# MCU.net
KiCad netlist of a schematic drawn in Altium Designer
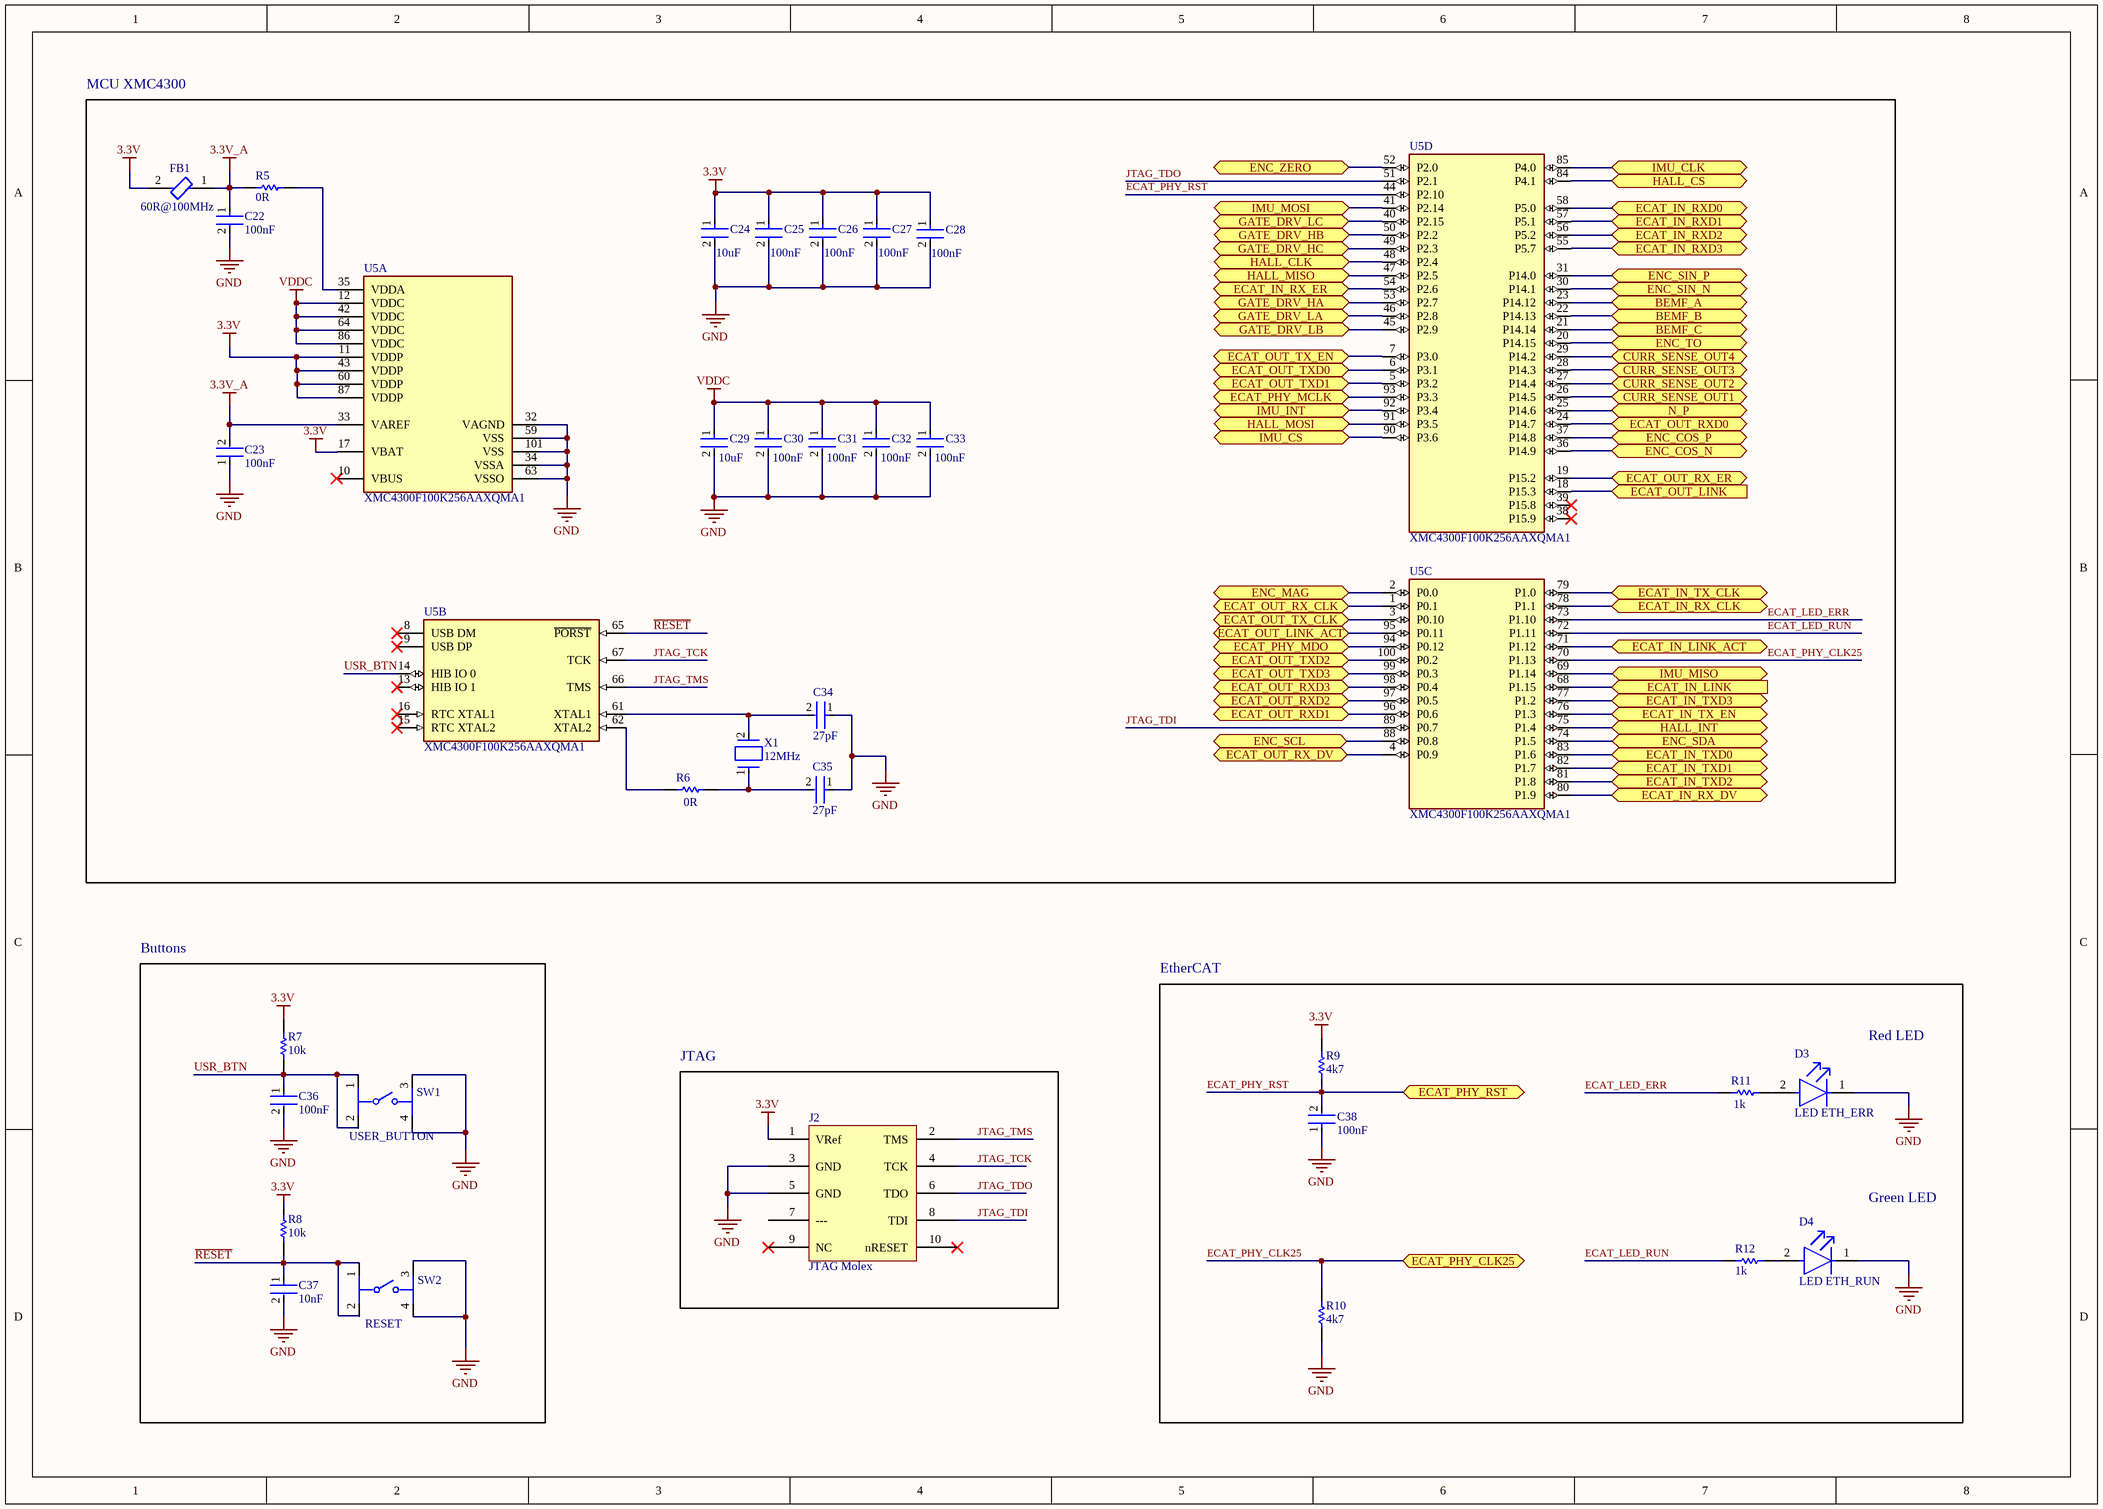
[diagram p0: MCU.SchDoc]

(export (version "E")
  (design (tool "Eeschema 10.0.6"))
  (components
    (comp (ref "C22")
      (value "100nF")
      (footprint "FP-C0805C-DN-MFG")
      (description "CAP CER 0.1UF 50V X7R 0805")
      (fields
        (field (name "MANUFACTURER PART NUMBER") "C0805C104K5RACTU")
        (field (name "MANUFACTURER") "KEMET")
      )
      (libsource (lib "Altium Content Vault") (part "b4654b650e69147ec39a6b967a45e02"))
    )
    (comp (ref "C23")
      (value "100nF")
      (footprint "FP-C0805C-DN-MFG")
      (description "CAP CER 0.1UF 50V X7R 0805")
      (fields
        (field (name "MANUFACTURER PART NUMBER") "C0805C104K5RACTU")
        (field (name "MANUFACTURER") "KEMET")
      )
      (libsource (lib "Altium Content Vault") (part "b4654b650e69147ec39a6b967a45e02"))
    )
    (comp (ref "C24")
      (value "10uF")
      (footprint "FP-C0805C-DN-MFG")
      (description "CAP CER 0.1UF 50V X7R 0805")
      (fields
        (field (name "MANUFACTURER PART NUMBER") "C0805C104K5RACTU")
        (field (name "MANUFACTURER") "KEMET")
      )
      (libsource (lib "Altium Content Vault") (part "b4654b650e69147ec39a6b967a45e02"))
    )
    (comp (ref "C25")
      (value "100nF")
      (footprint "FP-C0805C-DN-MFG")
      (description "CAP CER 0.1UF 50V X7R 0805")
      (fields
        (field (name "MANUFACTURER PART NUMBER") "C0805C104K5RACTU")
        (field (name "MANUFACTURER") "KEMET")
      )
      (libsource (lib "Altium Content Vault") (part "b4654b650e69147ec39a6b967a45e02"))
    )
    (comp (ref "C26")
      (value "100nF")
      (footprint "FP-C0805C-DN-MFG")
      (description "CAP CER 0.1UF 50V X7R 0805")
      (fields
        (field (name "MANUFACTURER PART NUMBER") "C0805C104K5RACTU")
        (field (name "MANUFACTURER") "KEMET")
      )
      (libsource (lib "Altium Content Vault") (part "b4654b650e69147ec39a6b967a45e02"))
    )
    (comp (ref "C27")
      (value "100nF")
      (footprint "FP-C0805C-DN-MFG")
      (description "CAP CER 0.1UF 50V X7R 0805")
      (fields
        (field (name "MANUFACTURER PART NUMBER") "C0805C104K5RACTU")
        (field (name "MANUFACTURER") "KEMET")
      )
      (libsource (lib "Altium Content Vault") (part "b4654b650e69147ec39a6b967a45e02"))
    )
    (comp (ref "C28")
      (value "100nF")
      (footprint "FP-C0805C-DN-MFG")
      (description "CAP CER 0.1UF 50V X7R 0805")
      (fields
        (field (name "MANUFACTURER PART NUMBER") "C0805C104K5RACTU")
        (field (name "MANUFACTURER") "KEMET")
      )
      (libsource (lib "Altium Content Vault") (part "b4654b650e69147ec39a6b967a45e02"))
    )
    (comp (ref "C29")
      (value "10uF")
      (footprint "FP-C0805C-DN-MFG")
      (description "CAP CER 0.1UF 50V X7R 0805")
      (fields
        (field (name "MANUFACTURER PART NUMBER") "C0805C104K5RACTU")
        (field (name "MANUFACTURER") "KEMET")
      )
      (libsource (lib "Altium Content Vault") (part "b4654b650e69147ec39a6b967a45e02"))
    )
    (comp (ref "C30")
      (value "100nF")
      (footprint "FP-C0805C-DN-MFG")
      (description "CAP CER 0.1UF 50V X7R 0805")
      (fields
        (field (name "MANUFACTURER PART NUMBER") "C0805C104K5RACTU")
        (field (name "MANUFACTURER") "KEMET")
      )
      (libsource (lib "Altium Content Vault") (part "b4654b650e69147ec39a6b967a45e02"))
    )
    (comp (ref "C31")
      (value "100nF")
      (footprint "FP-C0805C-DN-MFG")
      (description "CAP CER 0.1UF 50V X7R 0805")
      (fields
        (field (name "MANUFACTURER PART NUMBER") "C0805C104K5RACTU")
        (field (name "MANUFACTURER") "KEMET")
      )
      (libsource (lib "Altium Content Vault") (part "b4654b650e69147ec39a6b967a45e02"))
    )
    (comp (ref "C32")
      (value "100nF")
      (footprint "FP-C0805C-DN-MFG")
      (description "CAP CER 0.1UF 50V X7R 0805")
      (fields
        (field (name "MANUFACTURER PART NUMBER") "C0805C104K5RACTU")
        (field (name "MANUFACTURER") "KEMET")
      )
      (libsource (lib "Altium Content Vault") (part "b4654b650e69147ec39a6b967a45e02"))
    )
    (comp (ref "C33")
      (value "100nF")
      (footprint "FP-C0805C-DN-MFG")
      (description "CAP CER 0.1UF 50V X7R 0805")
      (fields
        (field (name "MANUFACTURER PART NUMBER") "C0805C104K5RACTU")
        (field (name "MANUFACTURER") "KEMET")
      )
      (libsource (lib "Altium Content Vault") (part "b4654b650e69147ec39a6b967a45e02"))
    )
    (comp (ref "C34")
      (value "27pF")
      (footprint "FP-C0805C-DN-MFG")
      (description "CAP CER 0.1UF 50V X7R 0805")
      (fields
        (field (name "MANUFACTURER PART NUMBER") "C0805C104K5RACTU")
        (field (name "MANUFACTURER") "KEMET")
      )
      (libsource (lib "Altium Content Vault") (part "b4654b650e69147ec39a6b967a45e02"))
    )
    (comp (ref "C35")
      (value "27pF")
      (footprint "FP-C0805C-DN-MFG")
      (description "CAP CER 0.1UF 50V X7R 0805")
      (fields
        (field (name "MANUFACTURER PART NUMBER") "C0805C104K5RACTU")
        (field (name "MANUFACTURER") "KEMET")
      )
      (libsource (lib "Altium Content Vault") (part "b4654b650e69147ec39a6b967a45e02"))
    )
    (comp (ref "C36")
      (value "100nF")
      (footprint "FP-C0805C-DN-MFG")
      (description "CAP CER 0.1UF 50V X7R 0805")
      (fields
        (field (name "MANUFACTURER PART NUMBER") "C0805C104K5RACTU")
        (field (name "MANUFACTURER") "KEMET")
      )
      (libsource (lib "Altium Content Vault") (part "b4654b650e69147ec39a6b967a45e02"))
    )
    (comp (ref "C37")
      (value "10nF")
      (footprint "FP-C0805C-DN-MFG")
      (description "CAP CER 0.1UF 50V X7R 0805")
      (fields
        (field (name "MANUFACTURER PART NUMBER") "C0805C104K5RACTU")
        (field (name "MANUFACTURER") "KEMET")
      )
      (libsource (lib "Altium Content Vault") (part "b4654b650e69147ec39a6b967a45e02"))
    )
    (comp (ref "C38")
      (value "100nF")
      (footprint "FP-C0805C-DN-MFG")
      (description "CAP CER 0.1UF 50V X7R 0805")
      (fields
        (field (name "MANUFACTURER PART NUMBER") "C0805C104K5RACTU")
        (field (name "MANUFACTURER") "KEMET")
      )
      (libsource (lib "Altium Content Vault") (part "b4654b650e69147ec39a6b967a45e02"))
    )
    (comp (ref "D3")
      (value "LED ETH_ERR")
      (footprint "FP-LTST-C191GKT-MFG")
      (description "KPHD-1608LVCGCK")
      (libsource (lib "Altium Content Vault") (part "8706943c75ba83719d021d2fdc84c58"))
    )
    (comp (ref "D4")
      (value "LED ETH_RUN")
      (footprint "FP-LTST-C191GKT-MFG")
      (description "KPHD-1608LVCGCK")
      (libsource (lib "Altium Content Vault") (part "8706943c75ba83719d021d2fdc84c58"))
    )
    (comp (ref "FB1")
      (value "60R@100MHz")
      (footprint "FP-BLM18-0_15-t0_8-IPC_C")
      (description "Chip Ferrite Bead, 0603, 60Ω @ 100MHz, 0.1Ω, , 1A\r\n\r\nBLM18PG600SH1D")
      (fields (field (name "TOLERANCE") "25%"))
      (libsource (lib "Altium Content Vault") (part "5f30dd21d616792df468990f7003faa"))
    )
    (comp (ref "J2")
      (value "JTAG Molex")
      (footprint "2X5_JTAG_HEADER")
      (description "MOLEX for JTAG, 5x2, 1,27 mm")
      (libsource (lib "CONNECTOR") (part "5x2_1,27mm_JTAG"))
    )
    (comp (ref "R5")
      (value "0R")
      (footprint "RESC2013X50X30LL20T20")
      (fields (field (name "MANUFACTURER") "Vishay Dale") (field (name "PART NUMBER") "CRCW08050000Z0EA"))
      (libsource (lib "Altium Content Vault") (part "RES"))
    )
    (comp (ref "R6")
      (value "0R")
      (footprint "RESC2013X50X30LL20T20")
      (fields (field (name "MANUFACTURER") "Vishay Dale") (field (name "PART NUMBER") "CRCW08050000Z0EA"))
      (libsource (lib "Altium Content Vault") (part "RES"))
    )
    (comp (ref "R7")
      (value "10k")
      (footprint "RESC2013X50X30LL20T20")
      (fields (field (name "MANUFACTURER") "Vishay Dale") (field (name "PART NUMBER") "CRCW08050000Z0EA"))
      (libsource (lib "Altium Content Vault") (part "RES"))
    )
    (comp (ref "R8")
      (value "10k")
      (footprint "RESC2013X50X30LL20T20")
      (fields (field (name "MANUFACTURER") "Vishay Dale") (field (name "PART NUMBER") "CRCW08050000Z0EA"))
      (libsource (lib "Altium Content Vault") (part "RES"))
    )
    (comp (ref "R9")
      (value "4k7")
      (footprint "RESC2013X50X30LL20T20")
      (description "0805")
      (fields (field (name "MANUFACTURER") "Vishay Dale") (field (name "PART NUMBER") "CRCW08050000Z0EA"))
      (libsource (lib "Altium Content Vault") (part "RES"))
    )
    (comp (ref "R10")
      (value "4k7")
      (footprint "RESC2013X50X30LL20T20")
      (description "0805")
      (fields (field (name "MANUFACTURER") "Vishay Dale") (field (name "PART NUMBER") "CRCW08050000Z0EA"))
      (libsource (lib "Altium Content Vault") (part "RES"))
    )
    (comp (ref "R11")
      (value "1k")
      (footprint "RESC2013X50X30LL20T20")
      (description "0805")
      (fields (field (name "MANUFACTURER") "Vishay Dale") (field (name "PART NUMBER") "CRCW08050000Z0EA"))
      (libsource (lib "Altium Content Vault") (part "RES"))
    )
    (comp (ref "R12")
      (value "1k")
      (footprint "RESC2013X50X30LL20T20")
      (description "0805")
      (fields (field (name "MANUFACTURER") "Vishay Dale") (field (name "PART NUMBER") "CRCW08050000Z0EA"))
      (libsource (lib "Altium Content Vault") (part "RES"))
    )
    (comp (ref "SW1")
      (value "USER_BUTTON")
      (footprint "FP-TL3305AF260QG-MFG")
      (description "SWITCH TACTILE SPST-NO 50MA 12V\r\n\r\nTL3305AF260QG")
      (libsource (lib "Altium Content Vault") (part "b8895f3f4cefb76e1819d2863dba89b"))
    )
    (comp (ref "SW2")
      (value "RESET")
      (footprint "FP-TL3305AF260QG-MFG")
      (description "SWITCH TACTILE SPST-NO 50MA 12V\r\n\r\nTL3305AF260QG")
      (libsource (lib "Altium Content Vault") (part "b8895f3f4cefb76e1819d2863dba89b"))
    )
    (comp (ref "U5")
      (value "XMC4300F100K256AAXQMA1")
      (footprint "FP-PG-LQFP-100-MFG")
      (description "IC MCU 32BIT 256KB FLASH 100LQFP")
      (libsource (lib "Altium Content Vault") (part "f9ed01fb84eaecf55d871649562e8ed"))
    )
    (comp (ref "X1")
      (value "12MHz")
      (footprint "FP-ABM3-MFG")
      (description "Crystal 12MHz SMD-2 5mm x 3.2mm")
      (fields (field (name "TOLERANCE") "20ppm"))
      (libsource (lib "Altium Content Vault") (part "c23a69dc6c9e2f18f2079038eb95dd1"))
    )
  )
  (nets
    (net (code "1") (name "/BEMF_A") (class "Default")
      (node (ref "U5") (pin "23") (pinfunction "P14.12_23") (pintype "bidirectional"))
    )
    (net (code "2") (name "/BEMF_B") (class "Default")
      (node (ref "U5") (pin "22") (pinfunction "P14.13_22") (pintype "bidirectional"))
    )
    (net (code "3") (name "/BEMF_C") (class "Default")
      (node (ref "U5") (pin "21") (pinfunction "P14.14_21") (pintype "bidirectional"))
    )
    (net (code "4") (name "/CURR_SENSE_OUT1") (class "Default")
      (node (ref "U5") (pin "26") (pinfunction "P14.5_26") (pintype "bidirectional"))
    )
    (net (code "5") (name "/CURR_SENSE_OUT2") (class "Default")
      (node (ref "U5") (pin "27") (pinfunction "P14.4_27") (pintype "bidirectional"))
    )
    (net (code "6") (name "/CURR_SENSE_OUT3") (class "Default")
      (node (ref "U5") (pin "28") (pinfunction "P14.3_28") (pintype "bidirectional"))
    )
    (net (code "7") (name "/CURR_SENSE_OUT4") (class "Default")
      (node (ref "U5") (pin "29") (pinfunction "P14.2_29") (pintype "bidirectional"))
    )
    (net (code "8") (name "/ECAT_IN_LINK") (class "Default")
      (node (ref "U5") (pin "68") (pinfunction "P1.15_68") (pintype "bidirectional"))
    )
    (net (code "9") (name "/ECAT_IN_LINK_ACT") (class "Default")
      (node (ref "U5") (pin "71") (pinfunction "P1.12_71") (pintype "bidirectional"))
    )
    (net (code "10") (name "/ECAT_IN_RXD0") (class "Default")
      (node (ref "U5") (pin "58") (pinfunction "P5.0_58") (pintype "bidirectional"))
    )
    (net (code "11") (name "/ECAT_IN_RXD1") (class "Default")
      (node (ref "U5") (pin "57") (pinfunction "P5.1_57") (pintype "bidirectional"))
    )
    (net (code "12") (name "/ECAT_IN_RXD2") (class "Default")
      (node (ref "U5") (pin "56") (pinfunction "P5.2_56") (pintype "bidirectional"))
    )
    (net (code "13") (name "/ECAT_IN_RXD3") (class "Default")
      (node (ref "U5") (pin "55") (pinfunction "P5.7_55") (pintype "bidirectional"))
    )
    (net (code "14") (name "/ECAT_IN_RX_CLK") (class "Default")
      (node (ref "U5") (pin "78") (pinfunction "P1.1_78") (pintype "bidirectional"))
    )
    (net (code "15") (name "/ECAT_IN_RX_DV") (class "Default")
      (node (ref "U5") (pin "80") (pinfunction "P1.9_80") (pintype "bidirectional"))
    )
    (net (code "16") (name "/ECAT_IN_RX_ER") (class "Default")
      (node (ref "U5") (pin "54") (pinfunction "P2.6_54") (pintype "bidirectional"))
    )
    (net (code "17") (name "/ECAT_IN_TXD0") (class "Default")
      (node (ref "U5") (pin "83") (pinfunction "P1.6_83") (pintype "bidirectional"))
    )
    (net (code "18") (name "/ECAT_IN_TXD1") (class "Default")
      (node (ref "U5") (pin "82") (pinfunction "P1.7_82") (pintype "bidirectional"))
    )
    (net (code "19") (name "/ECAT_IN_TXD2") (class "Default")
      (node (ref "U5") (pin "81") (pinfunction "P1.8_81") (pintype "bidirectional"))
    )
    (net (code "20") (name "/ECAT_IN_TXD3") (class "Default")
      (node (ref "U5") (pin "77") (pinfunction "P1.2_77") (pintype "bidirectional"))
    )
    (net (code "21") (name "/ECAT_IN_TX_CLK") (class "Default")
      (node (ref "U5") (pin "79") (pinfunction "P1.0_79") (pintype "bidirectional"))
    )
    (net (code "22") (name "/ECAT_IN_TX_EN") (class "Default")
      (node (ref "U5") (pin "76") (pinfunction "P1.3_76") (pintype "bidirectional"))
    )
    (net (code "23") (name "/ECAT_LED_ERR") (class "Default")
      (node (ref "R11") (pin "1") (pinfunction "1_1") (pintype "passive"))
      (node (ref "U5") (pin "73") (pinfunction "P1.10_73") (pintype "bidirectional"))
    )
    (net (code "24") (name "/ECAT_LED_RUN") (class "Default")
      (node (ref "R12") (pin "1") (pinfunction "1_1") (pintype "passive"))
      (node (ref "U5") (pin "72") (pinfunction "P1.11_72") (pintype "bidirectional"))
    )
    (net (code "25") (name "/ECAT_OUT_LINK") (class "Default")
      (node (ref "U5") (pin "18") (pinfunction "P15.3_18") (pintype "bidirectional"))
    )
    (net (code "26") (name "/ECAT_OUT_LINK_ACT") (class "Default")
      (node (ref "U5") (pin "95") (pinfunction "P0.11_95") (pintype "bidirectional"))
    )
    (net (code "27") (name "/ECAT_OUT_RXD0") (class "Default")
      (node (ref "U5") (pin "24") (pinfunction "P14.7_24") (pintype "bidirectional"))
    )
    (net (code "28") (name "/ECAT_OUT_RXD1") (class "Default")
      (node (ref "U5") (pin "96") (pinfunction "P0.6_96") (pintype "bidirectional"))
    )
    (net (code "29") (name "/ECAT_OUT_RXD2") (class "Default")
      (node (ref "U5") (pin "97") (pinfunction "P0.5_97") (pintype "bidirectional"))
    )
    (net (code "30") (name "/ECAT_OUT_RXD3") (class "Default")
      (node (ref "U5") (pin "98") (pinfunction "P0.4_98") (pintype "bidirectional"))
    )
    (net (code "31") (name "/ECAT_OUT_RX_CLK") (class "Default")
      (node (ref "U5") (pin "1") (pinfunction "P0.1_1") (pintype "bidirectional"))
    )
    (net (code "32") (name "/ECAT_OUT_RX_DV") (class "Default")
      (node (ref "U5") (pin "4") (pinfunction "P0.9_4") (pintype "bidirectional"))
    )
    (net (code "33") (name "/ECAT_OUT_RX_ER") (class "Default")
      (node (ref "U5") (pin "19") (pinfunction "P15.2_19") (pintype "bidirectional"))
    )
    (net (code "34") (name "/ECAT_OUT_TXD0") (class "Default")
      (node (ref "U5") (pin "6") (pinfunction "P3.1_6") (pintype "bidirectional"))
    )
    (net (code "35") (name "/ECAT_OUT_TXD1") (class "Default")
      (node (ref "U5") (pin "5") (pinfunction "P3.2_5") (pintype "bidirectional"))
    )
    (net (code "36") (name "/ECAT_OUT_TXD2") (class "Default")
      (node (ref "U5") (pin "100") (pinfunction "P0.2_100") (pintype "bidirectional"))
    )
    (net (code "37") (name "/ECAT_OUT_TXD3") (class "Default")
      (node (ref "U5") (pin "99") (pinfunction "P0.3_99") (pintype "bidirectional"))
    )
    (net (code "38") (name "/ECAT_OUT_TX_CLK") (class "Default")
      (node (ref "U5") (pin "3") (pinfunction "P0.10_3") (pintype "bidirectional"))
    )
    (net (code "39") (name "/ECAT_OUT_TX_EN") (class "Default")
      (node (ref "U5") (pin "7") (pinfunction "P3.0_7") (pintype "bidirectional"))
    )
    (net (code "40") (name "/ECAT_PHY_CLK25") (class "Default")
      (node (ref "R10") (pin "2") (pinfunction "2_2") (pintype "passive"))
      (node (ref "U5") (pin "70") (pinfunction "P1.13_70") (pintype "bidirectional"))
    )
    (net (code "41") (name "/ECAT_PHY_MCLK") (class "Default")
      (node (ref "U5") (pin "93") (pinfunction "P3.3_93") (pintype "bidirectional"))
    )
    (net (code "42") (name "/ECAT_PHY_MDO") (class "Default")
      (node (ref "U5") (pin "94") (pinfunction "P0.12_94") (pintype "bidirectional"))
    )
    (net (code "43") (name "/ECAT_PHY_RST") (class "Default")
      (node (ref "C38") (pin "2") (pinfunction "2_2") (pintype "passive"))
      (node (ref "R9") (pin "1") (pinfunction "1_1") (pintype "passive"))
      (node (ref "U5") (pin "44") (pinfunction "P2.10_44") (pintype "bidirectional"))
    )
    (net (code "44") (name "/ENC_COS_N") (class "Default")
      (node (ref "U5") (pin "36") (pinfunction "P14.9_36") (pintype "bidirectional"))
    )
    (net (code "45") (name "/ENC_COS_P") (class "Default")
      (node (ref "U5") (pin "37") (pinfunction "P14.8_37") (pintype "bidirectional"))
    )
    (net (code "46") (name "/ENC_MAG") (class "Default")
      (node (ref "U5") (pin "2") (pinfunction "P0.0_2") (pintype "bidirectional"))
    )
    (net (code "47") (name "/ENC_SCL") (class "Default")
      (node (ref "U5") (pin "88") (pinfunction "P0.8_88") (pintype "bidirectional"))
    )
    (net (code "48") (name "/ENC_SDA") (class "Default")
      (node (ref "U5") (pin "74") (pinfunction "P1.5_74") (pintype "bidirectional"))
    )
    (net (code "49") (name "/ENC_SIN_N") (class "Default")
      (node (ref "U5") (pin "30") (pinfunction "P14.1_30") (pintype "bidirectional"))
    )
    (net (code "50") (name "/ENC_SIN_P") (class "Default")
      (node (ref "U5") (pin "31") (pinfunction "P14.0_31") (pintype "bidirectional"))
    )
    (net (code "51") (name "/ENC_TO") (class "Default")
      (node (ref "U5") (pin "20") (pinfunction "P14.15_20") (pintype "bidirectional"))
    )
    (net (code "52") (name "/ENC_ZERO") (class "Default")
      (node (ref "U5") (pin "52") (pinfunction "P2.0_52") (pintype "bidirectional"))
    )
    (net (code "53") (name "/GATE_DRV_HA") (class "Default")
      (node (ref "U5") (pin "53") (pinfunction "P2.7_53") (pintype "bidirectional"))
    )
    (net (code "54") (name "/GATE_DRV_HB") (class "Default")
      (node (ref "U5") (pin "50") (pinfunction "P2.2_50") (pintype "bidirectional"))
    )
    (net (code "55") (name "/GATE_DRV_HC") (class "Default")
      (node (ref "U5") (pin "49") (pinfunction "P2.3_49") (pintype "bidirectional"))
    )
    (net (code "56") (name "/GATE_DRV_LA") (class "Default")
      (node (ref "U5") (pin "46") (pinfunction "P2.8_46") (pintype "bidirectional"))
    )
    (net (code "57") (name "/GATE_DRV_LB") (class "Default")
      (node (ref "U5") (pin "45") (pinfunction "P2.9_45") (pintype "bidirectional"))
    )
    (net (code "58") (name "/GATE_DRV_LC") (class "Default")
      (node (ref "U5") (pin "40") (pinfunction "P2.15_40") (pintype "bidirectional"))
    )
    (net (code "59") (name "/HALL_CLK") (class "Default")
      (node (ref "U5") (pin "48") (pinfunction "P2.4_48") (pintype "bidirectional"))
    )
    (net (code "60") (name "/HALL_CS") (class "Default")
      (node (ref "U5") (pin "84") (pinfunction "P4.1_84") (pintype "bidirectional"))
    )
    (net (code "61") (name "/HALL_INT") (class "Default")
      (node (ref "U5") (pin "75") (pinfunction "P1.4_75") (pintype "bidirectional"))
    )
    (net (code "62") (name "/HALL_MISO") (class "Default")
      (node (ref "U5") (pin "47") (pinfunction "P2.5_47") (pintype "bidirectional"))
    )
    (net (code "63") (name "/HALL_MOSI") (class "Default")
      (node (ref "U5") (pin "91") (pinfunction "P3.5_91") (pintype "bidirectional"))
    )
    (net (code "64") (name "/IMU_CLK") (class "Default")
      (node (ref "U5") (pin "85") (pinfunction "P4.0_85") (pintype "bidirectional"))
    )
    (net (code "65") (name "/IMU_CS") (class "Default")
      (node (ref "U5") (pin "90") (pinfunction "P3.6_90") (pintype "bidirectional"))
    )
    (net (code "66") (name "/IMU_INT") (class "Default")
      (node (ref "U5") (pin "92") (pinfunction "P3.4_92") (pintype "bidirectional"))
    )
    (net (code "67") (name "/IMU_MISO") (class "Default")
      (node (ref "U5") (pin "69") (pinfunction "P1.14_69") (pintype "bidirectional"))
    )
    (net (code "68") (name "/IMU_MOSI") (class "Default")
      (node (ref "U5") (pin "41") (pinfunction "P2.14_41") (pintype "bidirectional"))
    )
    (net (code "69") (name "/JTAG_TCK") (class "Default")
      (node (ref "J2") (pin "4") (pinfunction "TCK_4") (pintype "passive"))
      (node (ref "U5") (pin "67") (pinfunction "TCK_67") (pintype "input"))
    )
    (net (code "70") (name "/JTAG_TDI") (class "Default")
      (node (ref "J2") (pin "8") (pinfunction "TDI_8") (pintype "passive"))
      (node (ref "U5") (pin "89") (pinfunction "P0.7_89") (pintype "bidirectional"))
    )
    (net (code "71") (name "/JTAG_TDO") (class "Default")
      (node (ref "J2") (pin "6") (pinfunction "TDO_6") (pintype "passive"))
      (node (ref "U5") (pin "51") (pinfunction "P2.1_51") (pintype "bidirectional"))
    )
    (net (code "72") (name "/JTAG_TMS") (class "Default")
      (node (ref "J2") (pin "2") (pinfunction "TMS_2") (pintype "passive"))
      (node (ref "U5") (pin "66") (pinfunction "TMS_66") (pintype "input"))
    )
    (net (code "73") (name "/N_P") (class "Default")
      (node (ref "U5") (pin "25") (pinfunction "P14.6_25") (pintype "bidirectional"))
    )
    (net (code "74") (name "/USR_BTN") (class "Default")
      (node (ref "C36") (pin "1") (pinfunction "1_1") (pintype "passive"))
      (node (ref "R7") (pin "2") (pinfunction "2_2") (pintype "passive"))
      (node (ref "SW1") (pin "1") (pinfunction "1_1") (pintype "passive"))
      (node (ref "SW1") (pin "2") (pinfunction "2_2") (pintype "passive"))
      (node (ref "U5") (pin "14") (pinfunction "HIB_IO_0_14") (pintype "bidirectional"))
    )
    (net (code "75") (name "/~{RESET}") (class "Default")
      (node (ref "C37") (pin "1") (pinfunction "1_1") (pintype "passive"))
      (node (ref "R8") (pin "2") (pinfunction "2_2") (pintype "passive"))
      (node (ref "SW2") (pin "1") (pinfunction "1_1") (pintype "passive"))
      (node (ref "SW2") (pin "2") (pinfunction "2_2") (pintype "passive"))
      (node (ref "U5") (pin "65") (pinfunction "~{PORST}_65") (pintype "input"))
    )
    (net (code "76") (name "3.3V") (class "Default")
      (node (ref "C24") (pin "1") (pinfunction "1_1") (pintype "passive"))
      (node (ref "C25") (pin "1") (pinfunction "1_1") (pintype "passive"))
      (node (ref "C26") (pin "1") (pinfunction "1_1") (pintype "passive"))
      (node (ref "C27") (pin "1") (pinfunction "1_1") (pintype "passive"))
      (node (ref "C28") (pin "1") (pinfunction "1_1") (pintype "passive"))
      (node (ref "FB1") (pin "2") (pinfunction "2_2") (pintype "passive"))
      (node (ref "J2") (pin "1") (pinfunction "VRef_1") (pintype "passive"))
      (node (ref "R7") (pin "1") (pinfunction "1_1") (pintype "passive"))
      (node (ref "R8") (pin "1") (pinfunction "1_1") (pintype "passive"))
      (node (ref "R9") (pin "2") (pinfunction "2_2") (pintype "passive"))
      (node (ref "U5") (pin "11") (pinfunction "VDDP_11") (pintype "power_in"))
      (node (ref "U5") (pin "17") (pinfunction "VBAT_17") (pintype "power_in"))
      (node (ref "U5") (pin "43") (pinfunction "VDDP_43") (pintype "power_in"))
      (node (ref "U5") (pin "60") (pinfunction "VDDP_60") (pintype "power_in"))
      (node (ref "U5") (pin "87") (pinfunction "VDDP_87") (pintype "power_in"))
    )
    (net (code "77") (name "3.3V_A") (class "Default")
      (node (ref "C22") (pin "1") (pinfunction "1_1") (pintype "passive"))
      (node (ref "C23") (pin "2") (pinfunction "2_2") (pintype "passive"))
      (node (ref "FB1") (pin "1") (pinfunction "1_1") (pintype "passive"))
      (node (ref "R5") (pin "1") (pinfunction "1_1") (pintype "passive"))
      (node (ref "U5") (pin "33") (pinfunction "VAREF_33") (pintype "power_in"))
    )
    (net (code "78") (name "GND") (class "Default")
      (node (ref "C22") (pin "2") (pinfunction "2_2") (pintype "passive"))
      (node (ref "C23") (pin "1") (pinfunction "1_1") (pintype "passive"))
      (node (ref "C24") (pin "2") (pinfunction "2_2") (pintype "passive"))
      (node (ref "C25") (pin "2") (pinfunction "2_2") (pintype "passive"))
      (node (ref "C26") (pin "2") (pinfunction "2_2") (pintype "passive"))
      (node (ref "C27") (pin "2") (pinfunction "2_2") (pintype "passive"))
      (node (ref "C28") (pin "2") (pinfunction "2_2") (pintype "passive"))
      (node (ref "C29") (pin "2") (pinfunction "2_2") (pintype "passive"))
      (node (ref "C30") (pin "2") (pinfunction "2_2") (pintype "passive"))
      (node (ref "C31") (pin "2") (pinfunction "2_2") (pintype "passive"))
      (node (ref "C32") (pin "2") (pinfunction "2_2") (pintype "passive"))
      (node (ref "C33") (pin "2") (pinfunction "2_2") (pintype "passive"))
      (node (ref "C34") (pin "1") (pinfunction "1_1") (pintype "passive"))
      (node (ref "C35") (pin "1") (pinfunction "1_1") (pintype "passive"))
      (node (ref "C36") (pin "2") (pinfunction "2_2") (pintype "passive"))
      (node (ref "C37") (pin "2") (pinfunction "2_2") (pintype "passive"))
      (node (ref "C38") (pin "1") (pinfunction "1_1") (pintype "passive"))
      (node (ref "D3") (pin "1") (pinfunction "C_1") (pintype "passive"))
      (node (ref "D4") (pin "1") (pinfunction "C_1") (pintype "passive"))
      (node (ref "J2") (pin "3") (pinfunction "GND_3") (pintype "passive"))
      (node (ref "J2") (pin "5") (pinfunction "GND_5") (pintype "passive"))
      (node (ref "R10") (pin "1") (pinfunction "1_1") (pintype "passive"))
      (node (ref "SW1") (pin "3") (pinfunction "3_3") (pintype "passive"))
      (node (ref "SW1") (pin "4") (pinfunction "4_4") (pintype "passive"))
      (node (ref "SW2") (pin "3") (pinfunction "3_3") (pintype "passive"))
      (node (ref "SW2") (pin "4") (pinfunction "4_4") (pintype "passive"))
      (node (ref "U5") (pin "101") (pinfunction "VSS_101") (pintype "power_in"))
      (node (ref "U5") (pin "32") (pinfunction "VAGND_32") (pintype "power_in"))
      (node (ref "U5") (pin "34") (pinfunction "VSSA_34") (pintype "power_in"))
      (node (ref "U5") (pin "59") (pinfunction "VSS_59") (pintype "power_in"))
      (node (ref "U5") (pin "63") (pinfunction "VSSO_63") (pintype "power_in"))
    )
    (net (code "79") (name "Net-(C35-Pad2)") (class "Default")
      (node (ref "C35") (pin "2") (pinfunction "2_2") (pintype "passive"))
      (node (ref "R6") (pin "2") (pinfunction "2_2") (pintype "passive"))
      (node (ref "X1") (pin "1") (pinfunction "1_1") (pintype "passive"))
    )
    (net (code "80") (name "Net-(D3-A)") (class "Default")
      (node (ref "D3") (pin "2") (pinfunction "A_2") (pintype "passive"))
      (node (ref "R11") (pin "2") (pinfunction "2_2") (pintype "passive"))
    )
    (net (code "81") (name "Net-(D4-A)") (class "Default")
      (node (ref "D4") (pin "2") (pinfunction "A_2") (pintype "passive"))
      (node (ref "R12") (pin "2") (pinfunction "2_2") (pintype "passive"))
    )
    (net (code "82") (name "Net-(U5A-VDDA)") (class "Default")
      (node (ref "R5") (pin "2") (pinfunction "2_2") (pintype "passive"))
      (node (ref "U5") (pin "35") (pinfunction "VDDA_35") (pintype "power_in"))
    )
    (net (code "83") (name "Net-(U5B-XTAL1)") (class "Default")
      (node (ref "C34") (pin "2") (pinfunction "2_2") (pintype "passive"))
      (node (ref "U5") (pin "61") (pinfunction "XTAL1_61") (pintype "input"))
      (node (ref "X1") (pin "2") (pinfunction "2_2") (pintype "passive"))
    )
    (net (code "84") (name "Net-(U5B-XTAL2)") (class "Default")
      (node (ref "R6") (pin "1") (pinfunction "1_1") (pintype "passive"))
      (node (ref "U5") (pin "62") (pinfunction "XTAL2_62") (pintype "input"))
    )
    (net (code "85") (name "VDDC") (class "Default")
      (node (ref "C29") (pin "1") (pinfunction "1_1") (pintype "passive"))
      (node (ref "C30") (pin "1") (pinfunction "1_1") (pintype "passive"))
      (node (ref "C31") (pin "1") (pinfunction "1_1") (pintype "passive"))
      (node (ref "C32") (pin "1") (pinfunction "1_1") (pintype "passive"))
      (node (ref "C33") (pin "1") (pinfunction "1_1") (pintype "passive"))
      (node (ref "U5") (pin "12") (pinfunction "VDDC_12") (pintype "power_in"))
      (node (ref "U5") (pin "42") (pinfunction "VDDC_42") (pintype "power_in"))
      (node (ref "U5") (pin "64") (pinfunction "VDDC_64") (pintype "power_in"))
      (node (ref "U5") (pin "86") (pinfunction "VDDC_86") (pintype "power_in"))
    )
    (net (code "86") (name "unconnected-(J2-----Pad7)") (class "Default")
      (node (ref "J2") (pin "7") (pinfunction "---_7") (pintype "passive"))
    )
    (net (code "87") (name "unconnected-(J2-NC-Pad9)") (class "Default")
      (node (ref "J2") (pin "9") (pinfunction "NC_9") (pintype "passive+no_connect"))
    )
    (net (code "88") (name "unconnected-(J2-nRESET-Pad10)") (class "Default")
      (node (ref "J2") (pin "10") (pinfunction "nRESET_10") (pintype "passive+no_connect"))
    )
    (net (code "89") (name "unconnected-(U5A-VBUS-Pad10)") (class "Default")
      (node (ref "U5") (pin "10") (pinfunction "VBUS_10") (pintype "power_in+no_connect"))
    )
    (net (code "90") (name "unconnected-(U5B-HIB_IO_1-Pad13)") (class "Default")
      (node (ref "U5") (pin "13") (pinfunction "HIB_IO_1_13") (pintype "bidirectional+no_connect"))
    )
    (net (code "91") (name "unconnected-(U5B-RTC_XTAL1-Pad16)") (class "Default")
      (node (ref "U5") (pin "16") (pinfunction "RTC_XTAL1_16") (pintype "input+no_connect"))
    )
    (net (code "92") (name "unconnected-(U5B-RTC_XTAL2-Pad15)") (class "Default")
      (node (ref "U5") (pin "15") (pinfunction "RTC_XTAL2_15") (pintype "input+no_connect"))
    )
    (net (code "93") (name "unconnected-(U5B-USB_DM-Pad8)") (class "Default")
      (node (ref "U5") (pin "8") (pinfunction "USB_DM_8") (pintype "passive+no_connect"))
    )
    (net (code "94") (name "unconnected-(U5B-USB_DP-Pad9)") (class "Default")
      (node (ref "U5") (pin "9") (pinfunction "USB_DP_9") (pintype "passive+no_connect"))
    )
    (net (code "95") (name "unconnected-(U5D-P15.8-Pad39)") (class "Default")
      (node (ref "U5") (pin "39") (pinfunction "P15.8_39") (pintype "bidirectional+no_connect"))
    )
    (net (code "96") (name "unconnected-(U5D-P15.9-Pad38)") (class "Default")
      (node (ref "U5") (pin "38") (pinfunction "P15.9_38") (pintype "bidirectional+no_connect"))
    )
  )
)
